# power_rf.net
KiCad netlist of a schematic drawn in Altium Designer
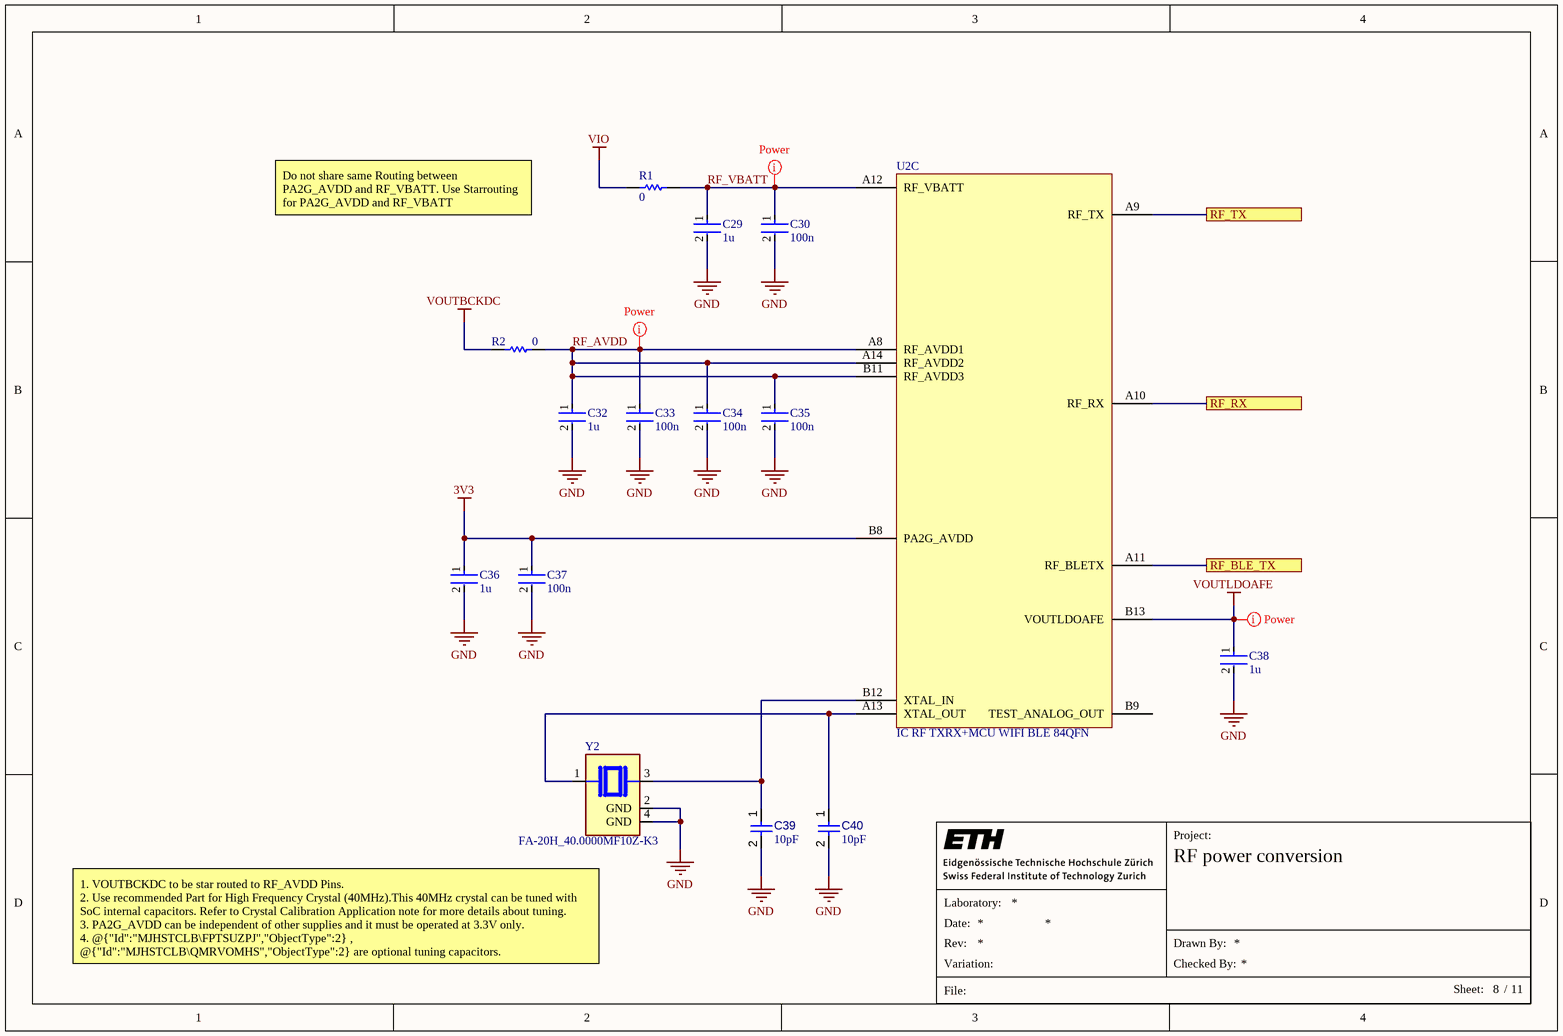
[diagram p0: power_rf.SchDoc]

(export (version "E")
  (design (tool "Eeschema 10.0.6"))
  (components
    (comp (ref "C29")
      (value "1u")
      (footprint "FP-GRM155-0_05-MFG")
      (description "Chip Multilayer Ceramic Capacitors for General Purpose, 0402, 1.0uF, X6S, 22%, 10%, 16V")
      (fields (field (name "TOLERANCE") "10%"))
      (libsource (lib "Altium Content Vault") (part "02cd4be3c70576c341d710602a673aa"))
    )
    (comp (ref "C30")
      (value "100n")
      (footprint "FP-GRT155-0_05-MFG")
      (description "Multi-Layer Ceramic Capacitor 100nF 50V X7R ±10% 0402 Paper T/R")
      (libsource (lib "Altium Content Vault") (part "02cd4be3c70576c341d710602a673aa"))
    )
    (comp (ref "C32")
      (value "1u")
      (footprint "FP-GRM155-0_05-MFG")
      (description "Chip Multilayer Ceramic Capacitors for General Purpose, 0402, 1.0uF, X6S, 22%, 10%, 16V")
      (fields (field (name "TOLERANCE") "10%"))
      (libsource (lib "Altium Content Vault") (part "02cd4be3c70576c341d710602a673aa"))
    )
    (comp (ref "C33")
      (value "100n")
      (footprint "FP-GRT155-0_05-MFG")
      (description "Multi-Layer Ceramic Capacitor 100nF 50V X7R ±10% 0402 Paper T/R")
      (libsource (lib "Altium Content Vault") (part "02cd4be3c70576c341d710602a673aa"))
    )
    (comp (ref "C34")
      (value "100n")
      (footprint "FP-GRT155-0_05-MFG")
      (description "Multi-Layer Ceramic Capacitor 100nF 50V X7R ±10% 0402 Paper T/R")
      (libsource (lib "Altium Content Vault") (part "02cd4be3c70576c341d710602a673aa"))
    )
    (comp (ref "C35")
      (value "100n")
      (footprint "FP-GRT155-0_05-MFG")
      (description "Multi-Layer Ceramic Capacitor 100nF 50V X7R ±10% 0402 Paper T/R")
      (libsource (lib "Altium Content Vault") (part "02cd4be3c70576c341d710602a673aa"))
    )
    (comp (ref "C36")
      (value "1u")
      (footprint "FP-GRM155-0_05-MFG")
      (description "Chip Multilayer Ceramic Capacitors for General Purpose, 0402, 1.0uF, X6S, 22%, 10%, 16V")
      (fields (field (name "TOLERANCE") "10%"))
      (libsource (lib "Altium Content Vault") (part "02cd4be3c70576c341d710602a673aa"))
    )
    (comp (ref "C37")
      (value "100n")
      (footprint "FP-GRT155-0_05-MFG")
      (description "Multi-Layer Ceramic Capacitor 100nF 50V X7R ±10% 0402 Paper T/R")
      (libsource (lib "Altium Content Vault") (part "02cd4be3c70576c341d710602a673aa"))
    )
    (comp (ref "C38")
      (value "1u")
      (footprint "FP-GRM155-0_05-MFG")
      (description "Chip Multilayer Ceramic Capacitors for General Purpose, 0402, 1.0uF, X6S, 22%, 10%, 16V")
      (fields (field (name "TOLERANCE") "10%"))
      (libsource (lib "Altium Content Vault") (part "02cd4be3c70576c341d710602a673aa"))
    )
    (comp (ref "C39")
      (value "10pF")
      (footprint "CAPC1005X55X30LL05T10")
      (description "Chip Capacitor, 10 pF, +/- 0.25 pF, 50 V, 0402 (1005 Metric)")
      (fields
        (field (name "TOLERANCE") "0.25%")
        (field (name "Comment") "Capacitor 10 pF +/- 0.25 pF 50 V 0402")
      )
      (libsource (lib "Cédric's Workspace") (part "CAP-NP-2"))
    )
    (comp (ref "C40")
      (value "10pF")
      (footprint "CAPC1005X55X30LL05T10")
      (description "Chip Capacitor, 10 pF, +/- 0.25 pF, 50 V, 0402 (1005 Metric)")
      (fields
        (field (name "TOLERANCE") "0.25%")
        (field (name "Comment") "Capacitor 10 pF +/- 0.25 pF 50 V 0402")
      )
      (libsource (lib "Cédric's Workspace") (part "CAP-NP-2"))
    )
    (comp (ref "R1")
      (value "0")
      (footprint "RESC1005X40X25ML05T10")
      (description "Chip Resistor, 0 Ohm, 0.063 W, -55 to 155 degC, 0402 (1005 Metric)")
      (fields (field (name "POWER") "63mW") (field (name "Comment") "Resistor 0R 0402 63 mW"))
      (libsource (lib "Cédric's Workspace") (part "RES-2"))
    )
    (comp (ref "R2")
      (value "0")
      (footprint "RESC1005X40X25ML05T10")
      (description "Chip Resistor, 0 Ohm, 0.063 W, -55 to 155 degC, 0402 (1005 Metric)")
      (fields (field (name "POWER") "63mW") (field (name "Comment") "Resistor 0R 0402 63 mW"))
      (libsource (lib "Cédric's Workspace") (part "RES-2"))
    )
    (comp (ref "U2")
      (value "IC RF TXRX+MCU WIFI BLE 84QFN")
      (footprint "SIWG917M110LGTBA")
      (libsource (lib "SiWG917") (part "SIWG917"))
    )
    (comp (ref "Y2")
      (value "FA-20H_40.0000MF10Z-K3")
      (footprint "FA-20H 40.0000MF10Z-K3:XTAL_FA-20H_40.0000MF10Z-K3")
      (fields (field (name "MF") "{'manufacturer': u'EPSON'}") (field (name "MP") "FA-20H 40.0000MF10Z-K3"))
      (libsource (lib "*") (part "FA-20H_40.0000MF10Z-K3"))
    )
  )
  (nets
    (net (code "1") (name "/RF_AVDD") (class "Default")
      (node (ref "C32") (pin "1") (pinfunction "1_1") (pintype "passive"))
      (node (ref "C33") (pin "1") (pinfunction "1_1") (pintype "passive"))
      (node (ref "C34") (pin "1") (pinfunction "1_1") (pintype "passive"))
      (node (ref "C35") (pin "1") (pinfunction "1_1") (pintype "passive"))
      (node (ref "R2") (pin "2") (pinfunction "2_2") (pintype "passive"))
      (node (ref "U2") (pin "A14") (pinfunction "RF_AVDD2_A14") (pintype "power_in"))
      (node (ref "U2") (pin "A8") (pinfunction "RF_AVDD1_A8") (pintype "power_in"))
      (node (ref "U2") (pin "B11") (pinfunction "RF_AVDD3_B11") (pintype "power_in"))
    )
    (net (code "2") (name "/RF_BLE_TX") (class "Default")
      (node (ref "U2") (pin "A11") (pinfunction "RF_BLETX_A11") (pintype "passive"))
    )
    (net (code "3") (name "/RF_RX") (class "Default")
      (node (ref "U2") (pin "A10") (pinfunction "RF_RX_A10") (pintype "passive"))
    )
    (net (code "4") (name "/RF_TX") (class "Default")
      (node (ref "U2") (pin "A9") (pinfunction "RF_TX_A9") (pintype "passive"))
    )
    (net (code "5") (name "/RF_VBATT") (class "Default")
      (node (ref "C29") (pin "1") (pinfunction "1_1") (pintype "passive"))
      (node (ref "C30") (pin "1") (pinfunction "1_1") (pintype "passive"))
      (node (ref "R1") (pin "2") (pinfunction "2_2") (pintype "passive"))
      (node (ref "U2") (pin "A12") (pinfunction "RF_VBATT_A12") (pintype "power_in"))
    )
    (net (code "6") (name "3V3") (class "Default")
      (node (ref "C36") (pin "1") (pinfunction "1_1") (pintype "passive"))
      (node (ref "C37") (pin "1") (pinfunction "1_1") (pintype "passive"))
      (node (ref "U2") (pin "B8") (pinfunction "PA2G_AVDD_B8") (pintype "power_in"))
    )
    (net (code "7") (name "GND") (class "Default")
      (node (ref "C29") (pin "2") (pinfunction "2_2") (pintype "passive"))
      (node (ref "C30") (pin "2") (pinfunction "2_2") (pintype "passive"))
      (node (ref "C32") (pin "2") (pinfunction "2_2") (pintype "passive"))
      (node (ref "C33") (pin "2") (pinfunction "2_2") (pintype "passive"))
      (node (ref "C34") (pin "2") (pinfunction "2_2") (pintype "passive"))
      (node (ref "C35") (pin "2") (pinfunction "2_2") (pintype "passive"))
      (node (ref "C36") (pin "2") (pinfunction "2_2") (pintype "passive"))
      (node (ref "C37") (pin "2") (pinfunction "2_2") (pintype "passive"))
      (node (ref "C38") (pin "2") (pinfunction "2_2") (pintype "passive"))
      (node (ref "C39") (pin "2") (pinfunction "2_2") (pintype "passive"))
      (node (ref "C40") (pin "2") (pinfunction "2_2") (pintype "passive"))
      (node (ref "Y2") (pin "2") (pinfunction "GND_2") (pintype "power_in"))
      (node (ref "Y2") (pin "4") (pinfunction "GND_4") (pintype "power_in"))
    )
    (net (code "8") (name "Net-(U2C-XTAL_IN)") (class "Default")
      (node (ref "C39") (pin "1") (pinfunction "1_1") (pintype "passive"))
      (node (ref "U2") (pin "B12") (pinfunction "XTAL_IN_B12") (pintype "passive"))
      (node (ref "Y2") (pin "3") (pinfunction "2_3") (pintype "passive"))
    )
    (net (code "9") (name "Net-(U2C-XTAL_OUT)") (class "Default")
      (node (ref "C40") (pin "1") (pinfunction "1_1") (pintype "passive"))
      (node (ref "U2") (pin "A13") (pinfunction "XTAL_OUT_A13") (pintype "passive"))
      (node (ref "Y2") (pin "1") (pinfunction "1_1") (pintype "passive"))
    )
    (net (code "10") (name "VIO") (class "Default")
      (node (ref "R1") (pin "1") (pinfunction "1_1") (pintype "passive"))
    )
    (net (code "11") (name "VOUTBCKDC") (class "Default")
      (node (ref "R2") (pin "1") (pinfunction "1_1") (pintype "passive"))
    )
    (net (code "12") (name "VOUTLDOAFE") (class "Default")
      (node (ref "C38") (pin "1") (pinfunction "1_1") (pintype "passive"))
      (node (ref "U2") (pin "B13") (pinfunction "VOUTLDOAFE_B13") (pintype "power_in"))
    )
    (net (code "13") (name "unconnected-(U2C-TEST_ANALOG_OUT-PadB9)") (class "Default")
      (node (ref "U2") (pin "B9") (pinfunction "TEST_ANALOG_OUT_B9") (pintype "passive"))
    )
  )
)
